# EARM01.net
KiCad netlist of a schematic drawn in EAGLE
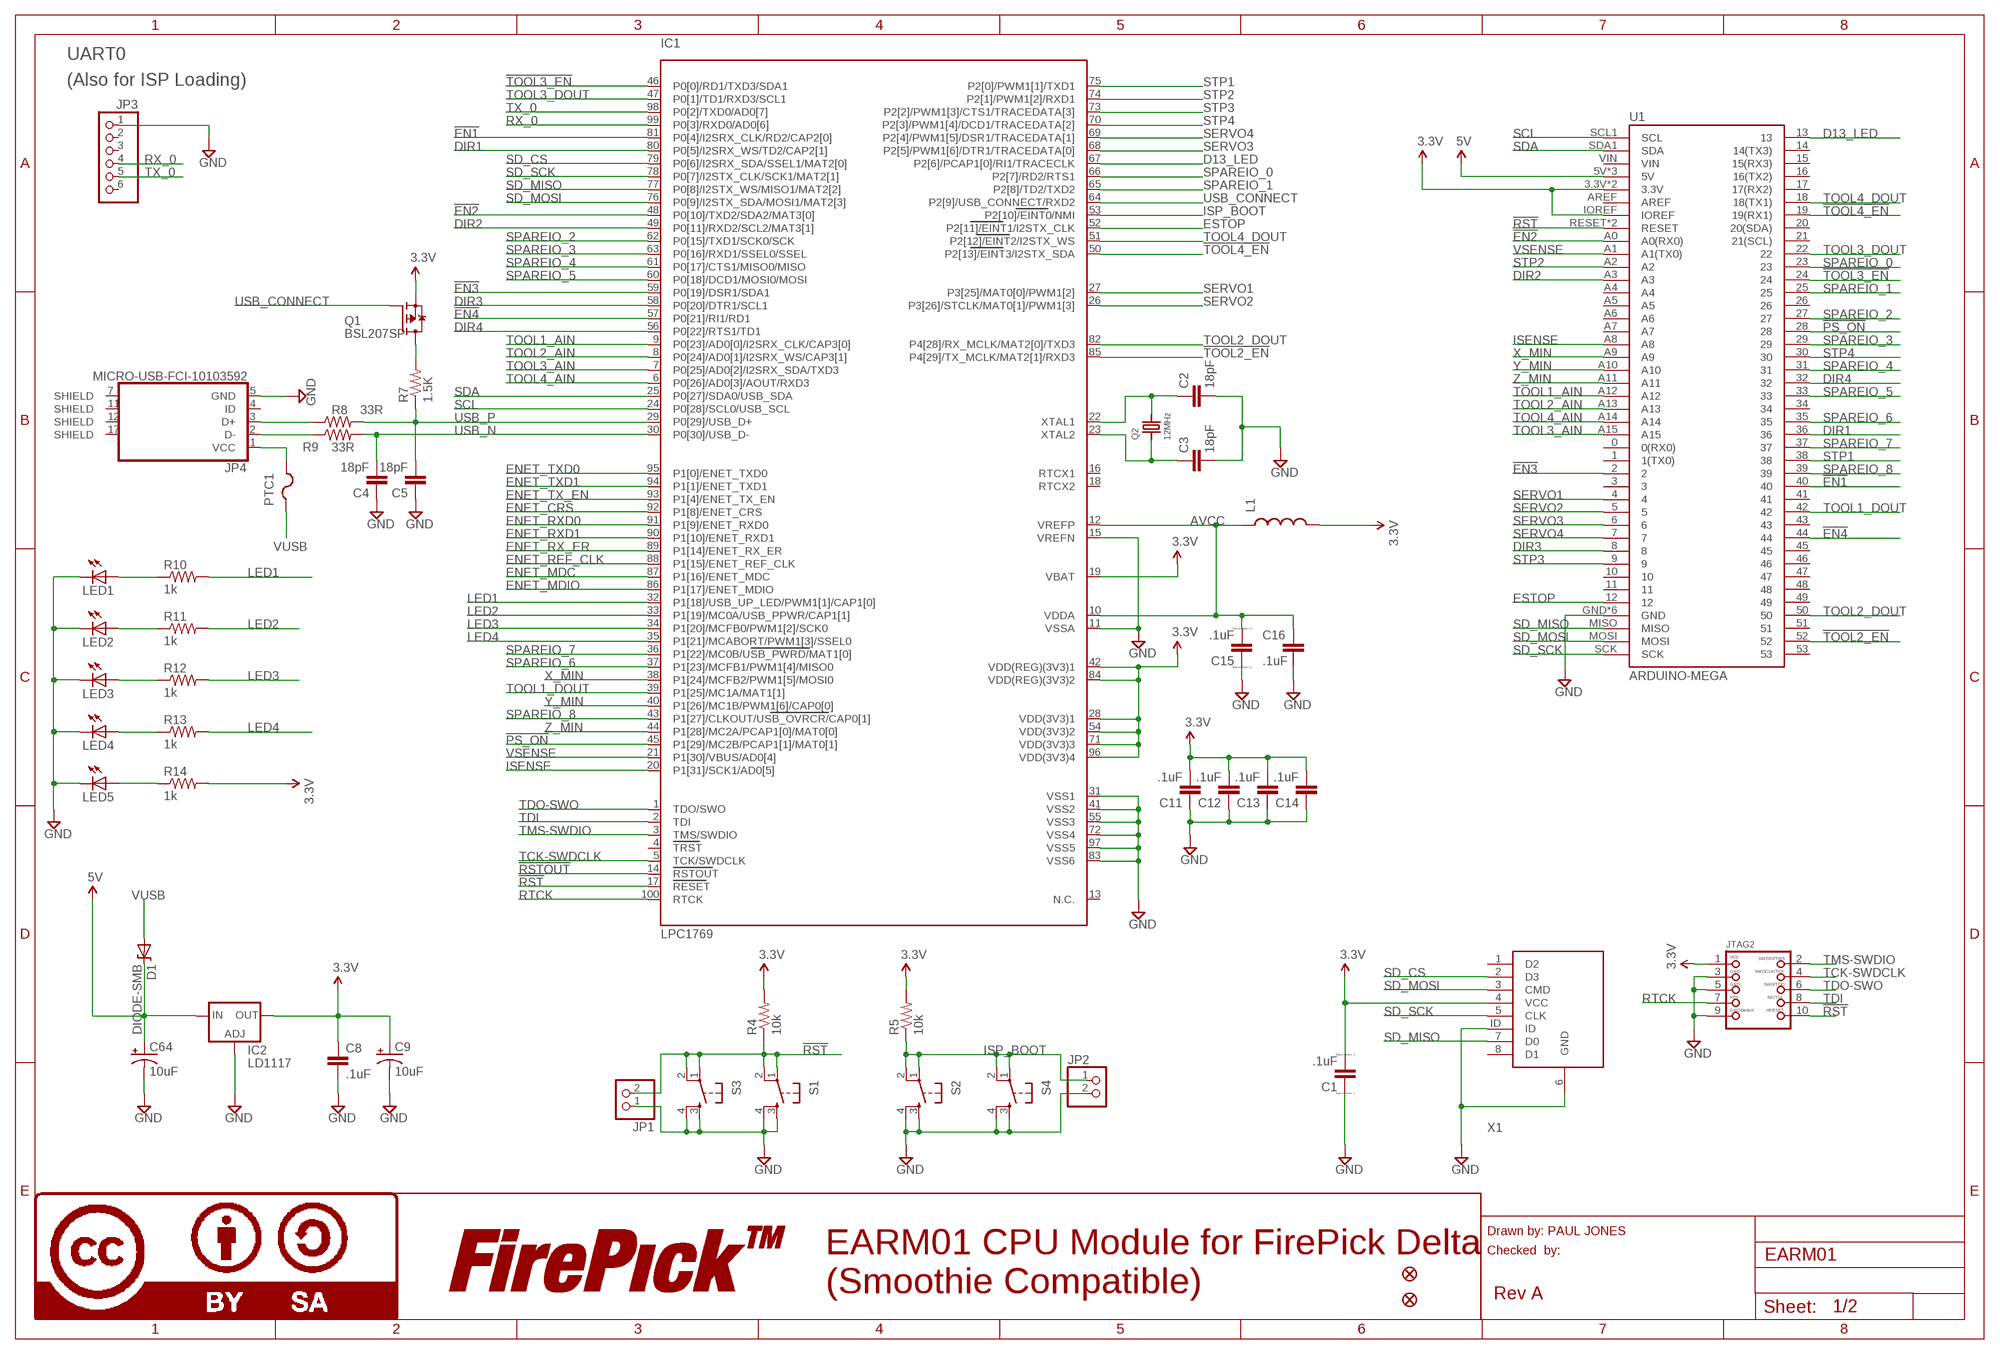
[diagram p0: schematic, sheet 1]
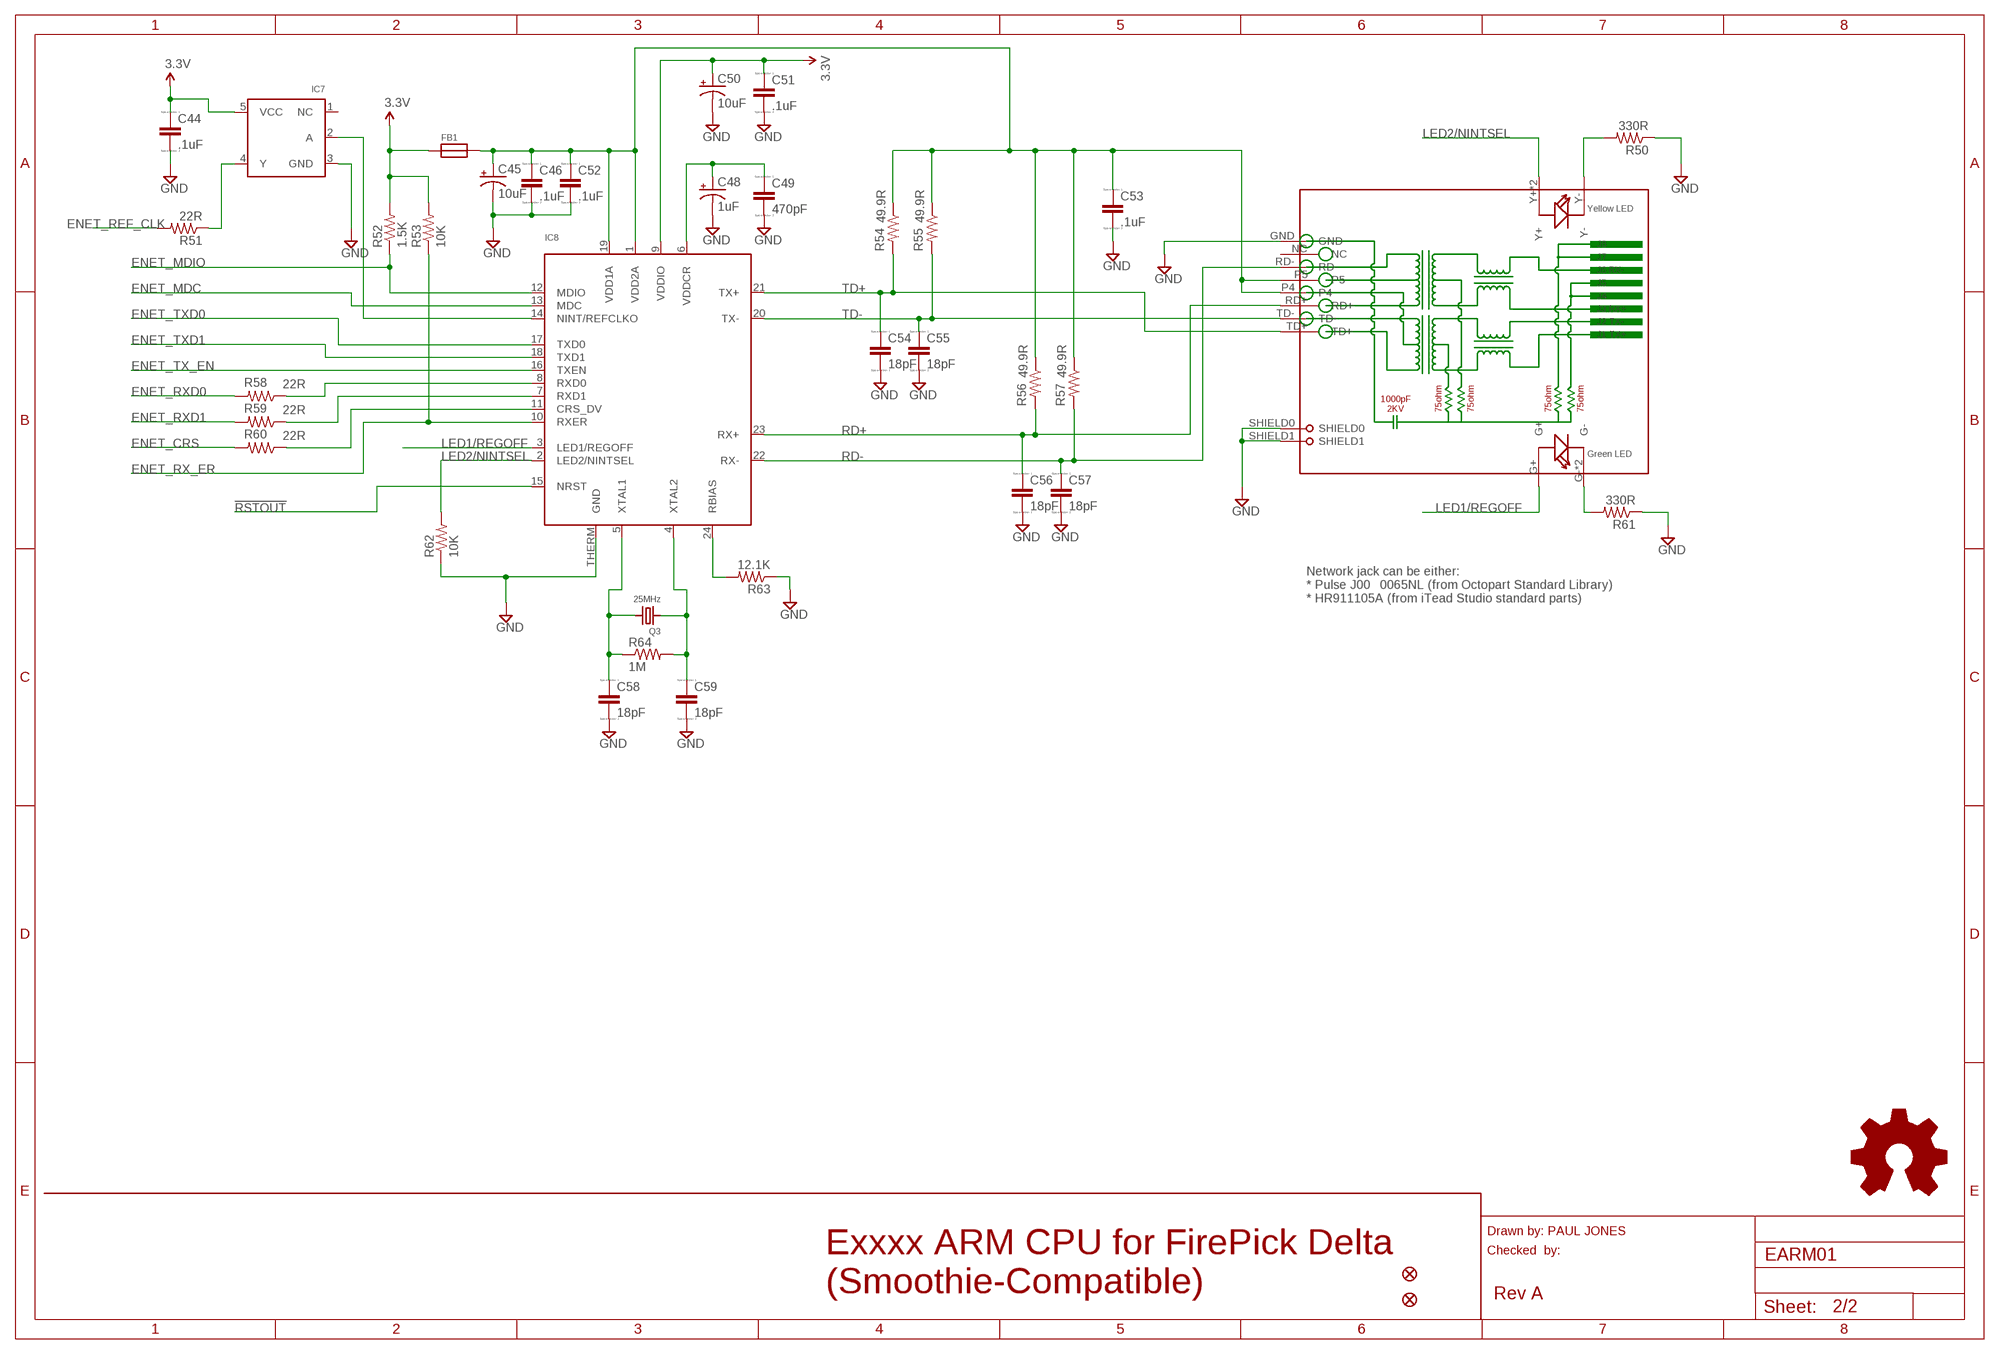
[diagram p1: schematic, sheet 2]

(export (version "E")
  (design (tool "Eeschema 10.0.6"))
  (components
    (comp (ref "C44")
      (value ".1uF")
      (footprint "eagle-import:C0603")
      (libsource (lib "eagle-import") (part "resistor_C-EUC0603"))
    )
    (comp (ref "C45")
      (value "10uF")
      (footprint "eagle-import:EIA3216")
      (libsource (lib "eagle-import") (part "CAP_POL1206"))
    )
    (comp (ref "C46")
      (value ".1uF")
      (footprint "eagle-import:C0603")
      (libsource (lib "eagle-import") (part "resistor_C-EUC0603"))
    )
    (comp (ref "C48")
      (value "1uF")
      (footprint "eagle-import:EIA3216")
      (libsource (lib "eagle-import") (part "CAP_POL1206"))
    )
    (comp (ref "C49")
      (value "470pF")
      (footprint "eagle-import:C0603K")
      (libsource (lib "eagle-import") (part "resistor_C-EUC0603K"))
    )
    (comp (ref "C50")
      (value "10uF")
      (footprint "eagle-import:EIA3216")
      (libsource (lib "eagle-import") (part "CAP_POL1206"))
    )
    (comp (ref "C51")
      (value ".1uF")
      (footprint "eagle-import:C0603")
      (libsource (lib "eagle-import") (part "resistor_C-EUC0603"))
    )
    (comp (ref "C52")
      (value ".1uF")
      (footprint "eagle-import:C0603")
      (libsource (lib "eagle-import") (part "resistor_C-EUC0603"))
    )
    (comp (ref "C53")
      (value ".1uF")
      (footprint "eagle-import:C0603")
      (libsource (lib "eagle-import") (part "resistor_C-EUC0603"))
    )
    (comp (ref "C54")
      (value "18pF")
      (footprint "eagle-import:C0603")
      (libsource (lib "eagle-import") (part "resistor_C-EUC0603"))
    )
    (comp (ref "C55")
      (value "18pF")
      (footprint "eagle-import:C0603")
      (libsource (lib "eagle-import") (part "resistor_C-EUC0603"))
    )
    (comp (ref "C56")
      (value "18pF")
      (footprint "eagle-import:C0603")
      (libsource (lib "eagle-import") (part "resistor_C-EUC0603"))
    )
    (comp (ref "C57")
      (value "18pF")
      (footprint "eagle-import:C0603")
      (libsource (lib "eagle-import") (part "resistor_C-EUC0603"))
    )
    (comp (ref "C58")
      (value "18pF")
      (footprint "eagle-import:C0603")
      (libsource (lib "eagle-import") (part "resistor_C-EUC0603"))
    )
    (comp (ref "C59")
      (value "18pF")
      (footprint "eagle-import:C0603")
      (libsource (lib "eagle-import") (part "resistor_C-EUC0603"))
    )
    (comp (ref "FB1")
      (value "FERRITE")
      (footprint "eagle-import:0603")
      (libsource (lib "eagle-import") (part "FERRITE"))
    )
    (comp (ref "FID17")
      (value "FIDUCIAL1X2")
      (footprint "eagle-import:FIDUCIAL-1X2")
      (libsource (lib "eagle-import") (part "FIDUCIAL1X2"))
    )
    (comp (ref "FID18")
      (value "FIDUCIAL1X2")
      (footprint "eagle-import:FIDUCIAL-1X2")
      (libsource (lib "eagle-import") (part "FIDUCIAL1X2"))
    )
    (comp (ref "IC7")
      (value "74LVC1G04")
      (footprint "eagle-import:SOT23-5")
      (libsource (lib "eagle-import") (part "74LVC1G04"))
    )
    (comp (ref "IC8")
      (value "LAN8720")
      (footprint "eagle-import:QFN24_4MM")
      (libsource (lib "eagle-import") (part "LAN8720"))
    )
    (comp (ref "LOGO10")
      (value "LOGO-OSHWSMALL")
      (footprint "eagle-import:LOGO-OSHW-SMALL")
      (libsource (lib "eagle-import") (part "LOGO-OSHWSMALL"))
    )
    (comp (ref "Q3")
      (value "25MHz")
      (footprint "eagle-import:CRYSTAL_3.2X2.5")
      (libsource (lib "eagle-import") (part "CRYSTALTHIN"))
    )
    (comp (ref "R50")
      (value "330R")
      (footprint "eagle-import:R0603")
      (libsource (lib "eagle-import") (part "R-US_R0603"))
    )
    (comp (ref "R51")
      (value "22R")
      (footprint "eagle-import:R0603")
      (libsource (lib "eagle-import") (part "R-US_R0603"))
    )
    (comp (ref "R52")
      (value "1.5K")
      (footprint "eagle-import:R0603")
      (libsource (lib "eagle-import") (part "R-US_R0603"))
    )
    (comp (ref "R53")
      (value "10K")
      (footprint "eagle-import:R0603")
      (libsource (lib "eagle-import") (part "R-US_R0603"))
    )
    (comp (ref "R54")
      (value "49.9R")
      (footprint "eagle-import:R0603")
      (libsource (lib "eagle-import") (part "R-US_R0603"))
    )
    (comp (ref "R55")
      (value "49.9R")
      (footprint "eagle-import:R0603")
      (libsource (lib "eagle-import") (part "R-US_R0603"))
    )
    (comp (ref "R56")
      (value "49.9R")
      (footprint "eagle-import:R0603")
      (libsource (lib "eagle-import") (part "R-US_R0603"))
    )
    (comp (ref "R57")
      (value "49.9R")
      (footprint "eagle-import:R0603")
      (libsource (lib "eagle-import") (part "R-US_R0603"))
    )
    (comp (ref "R58")
      (value "22R")
      (footprint "eagle-import:R0603")
      (libsource (lib "eagle-import") (part "R-US_R0603"))
    )
    (comp (ref "R59")
      (value "22R")
      (footprint "eagle-import:R0603")
      (libsource (lib "eagle-import") (part "R-US_R0603"))
    )
    (comp (ref "R60")
      (value "22R")
      (footprint "eagle-import:R0603")
      (libsource (lib "eagle-import") (part "R-US_R0603"))
    )
    (comp (ref "R61")
      (value "330R")
      (footprint "eagle-import:R0603")
      (libsource (lib "eagle-import") (part "R-US_R0603"))
    )
    (comp (ref "R62")
      (value "10K")
      (footprint "eagle-import:R0603")
      (libsource (lib "eagle-import") (part "R-US_R0603"))
    )
    (comp (ref "R63")
      (value "12.1K")
      (footprint "eagle-import:R0603")
      (libsource (lib "eagle-import") (part "R-US_R0603"))
    )
    (comp (ref "R64")
      (value "1M")
      (footprint "eagle-import:R0603")
      (libsource (lib "eagle-import") (part "R-US_R0603"))
    )
    (comp (ref "RJ1")
      (value "HR911105A")
      (footprint "eagle-import:HR911105A")
      (libsource (lib "eagle-import") (part "HR911105A"))
    )
    (comp (ref "C1")
      (value ".1uF")
      (footprint "eagle-import:C0603")
      (libsource (lib "eagle-import") (part "resistor_C-EUC0603"))
    )
    (comp (ref "C2")
      (value "18pF")
      (footprint "eagle-import:C0603")
      (libsource (lib "eagle-import") (part "C-EUC0603"))
    )
    (comp (ref "C3")
      (value "18pF")
      (footprint "eagle-import:C0603")
      (libsource (lib "eagle-import") (part "C-EUC0603"))
    )
    (comp (ref "C4")
      (value "18pF")
      (footprint "eagle-import:C0603")
      (libsource (lib "eagle-import") (part "C-EUC0603"))
    )
    (comp (ref "C5")
      (value "18pF")
      (footprint "eagle-import:C0603")
      (libsource (lib "eagle-import") (part "C-EUC0603"))
    )
    (comp (ref "C8")
      (value ".1uF")
      (footprint "eagle-import:C0603")
      (libsource (lib "eagle-import") (part "C-EUC0603"))
    )
    (comp (ref "C9")
      (value "10uF")
      (footprint "eagle-import:EIA3216")
      (libsource (lib "eagle-import") (part "CAP_POL1206"))
    )
    (comp (ref "C11")
      (value ".1uF")
      (footprint "eagle-import:C0603")
      (libsource (lib "eagle-import") (part "C-EUC0603"))
    )
    (comp (ref "C12")
      (value ".1uF")
      (footprint "eagle-import:C0603")
      (libsource (lib "eagle-import") (part "C-EUC0603"))
    )
    (comp (ref "C13")
      (value ".1uF")
      (footprint "eagle-import:C0603")
      (libsource (lib "eagle-import") (part "C-EUC0603"))
    )
    (comp (ref "C14")
      (value ".1uF")
      (footprint "eagle-import:C0603")
      (libsource (lib "eagle-import") (part "C-EUC0603"))
    )
    (comp (ref "C15")
      (value ".1uF")
      (footprint "eagle-import:C0603")
      (libsource (lib "eagle-import") (part "resistor_C-EUC0603"))
    )
    (comp (ref "C16")
      (value ".1uF")
      (footprint "eagle-import:C0603")
      (libsource (lib "eagle-import") (part "C-EUC0603"))
    )
    (comp (ref "C64")
      (value "10uF")
      (footprint "eagle-import:EIA3216")
      (libsource (lib "eagle-import") (part "CAP_POL1206"))
    )
    (comp (ref "D1")
      (value "DIODE-SMB")
      (footprint "eagle-import:SMB-DIODE")
      (libsource (lib "eagle-import") (part "DIODE-ZENERSMB"))
    )
    (comp (ref "FID5")
      (value "FIDUCIAL1X2")
      (footprint "eagle-import:FIDUCIAL-1X2")
      (libsource (lib "eagle-import") (part "FIDUCIAL1X2"))
    )
    (comp (ref "FID6")
      (value "FIDUCIAL1X2")
      (footprint "eagle-import:FIDUCIAL-1X2")
      (libsource (lib "eagle-import") (part "FIDUCIAL1X2"))
    )
    (comp (ref "IC1")
      (value "LPC1769")
      (footprint "eagle-import:LQFP100")
      (libsource (lib "eagle-import") (part "LPC1768"))
    )
    (comp (ref "IC2")
      (value "LD1117")
      (footprint "eagle-import:SOT223")
      (libsource (lib "eagle-import") (part "LD117A?S12TR"))
    )
    (comp (ref "JP1")
      (value "PINHD-1X2")
      (footprint "eagle-import:1X02")
      (libsource (lib "eagle-import") (part "PINHD-1X2"))
    )
    (comp (ref "JP2")
      (value "PINHD-1X2")
      (footprint "eagle-import:1X02")
      (libsource (lib "eagle-import") (part "PINHD-1X2"))
    )
    (comp (ref "JP3")
      (value "PINHD-1X6")
      (footprint "eagle-import:1X06")
      (libsource (lib "eagle-import") (part "PINHD-1X6"))
    )
    (comp (ref "JP4")
      (value "MICRO-USB-FCI-10103592")
      (footprint "eagle-import:MICRO-USB-FCI-10103592")
      (libsource (lib "eagle-import") (part "MICRO-USB-FCI-10103592"))
    )
    (comp (ref "JTAG2")
      (value "JTAG-CORTEXM3")
      (footprint "eagle-import:2X05_1.27MM_SMT")
      (libsource (lib "eagle-import") (part "JTAG-CORTEXM3"))
    )
    (comp (ref "L1")
      (value "INDUCTOR0603")
      (footprint "eagle-import:0603")
      (libsource (lib "eagle-import") (part "INDUCTOR0603"))
    )
    (comp (ref "LED1")
      (value "LED")
      (footprint "eagle-import:LED-1206-BOTTOM")
      (libsource (lib "eagle-import") (part "LED"))
    )
    (comp (ref "LED2")
      (value "LED")
      (footprint "eagle-import:LED-1206-BOTTOM")
      (libsource (lib "eagle-import") (part "LED"))
    )
    (comp (ref "LED3")
      (value "LED")
      (footprint "eagle-import:LED-1206-BOTTOM")
      (libsource (lib "eagle-import") (part "LED"))
    )
    (comp (ref "LED4")
      (value "LED")
      (footprint "eagle-import:LED-1206-BOTTOM")
      (libsource (lib "eagle-import") (part "LED"))
    )
    (comp (ref "LED5")
      (value "LED")
      (footprint "eagle-import:LED-1206-BOTTOM")
      (libsource (lib "eagle-import") (part "LED"))
    )
    (comp (ref "LOGO4")
      (value "LOGO-FIREPICKMEDIUM")
      (footprint "eagle-import:LOGO-FIREPICK-MEDIUM")
      (libsource (lib "eagle-import") (part "LOGO-FIREPICKMEDIUM"))
    )
    (comp (ref "LOGO6")
      (value "LOGO-CC-BY-SAMEDIUM")
      (footprint "eagle-import:LOGO-CC-BY-SA-MEDIUM")
      (libsource (lib "eagle-import") (part "LOGO-CC-BY-SAMEDIUM"))
    )
    (comp (ref "PTC1")
      (value "PTCFUSE-1812")
      (footprint "eagle-import:1812")
      (libsource (lib "eagle-import") (part "PTCFUSE-1812"))
    )
    (comp (ref "Q1")
      (value "BSL207SP")
      (footprint "eagle-import:SC74_INFINEON")
      (libsource (lib "eagle-import") (part "BSL207SP"))
    )
    (comp (ref "Q2")
      (value "12MHz")
      (footprint "eagle-import:CRYSTAL_3.2X2.5")
      (libsource (lib "eagle-import") (part "CRYSTALTHIN"))
    )
    (comp (ref "R4")
      (value "10k")
      (footprint "eagle-import:R0603")
      (libsource (lib "eagle-import") (part "R-US_R0603"))
    )
    (comp (ref "R5")
      (value "10k")
      (footprint "eagle-import:R0603")
      (libsource (lib "eagle-import") (part "R-US_R0603"))
    )
    (comp (ref "R7")
      (value "1.5K")
      (footprint "eagle-import:R0603")
      (libsource (lib "eagle-import") (part "R-US_R0603"))
    )
    (comp (ref "R8")
      (value "33R")
      (footprint "eagle-import:R0603")
      (libsource (lib "eagle-import") (part "R-US_R0603"))
    )
    (comp (ref "R9")
      (value "33R")
      (footprint "eagle-import:R0603")
      (libsource (lib "eagle-import") (part "R-US_R0603"))
    )
    (comp (ref "R10")
      (value "1k")
      (footprint "eagle-import:R0603")
      (libsource (lib "eagle-import") (part "R-US_R0603"))
    )
    (comp (ref "R11")
      (value "1k")
      (footprint "eagle-import:R0603")
      (libsource (lib "eagle-import") (part "R-US_R0603"))
    )
    (comp (ref "R12")
      (value "1k")
      (footprint "eagle-import:R0603")
      (libsource (lib "eagle-import") (part "R-US_R0603"))
    )
    (comp (ref "R13")
      (value "1k")
      (footprint "eagle-import:R0603")
      (libsource (lib "eagle-import") (part "R-US_R0603"))
    )
    (comp (ref "R14")
      (value "1k")
      (footprint "eagle-import:R0603")
      (libsource (lib "eagle-import") (part "R-US_R0603"))
    )
    (comp (ref "S1")
      (value "TAC_SWITCHSMD")
      (footprint "eagle-import:TACTILE_SWITCH_SMD")
      (libsource (lib "eagle-import") (part "TAC_SWITCHSMD"))
    )
    (comp (ref "S2")
      (value "TAC_SWITCHSMD")
      (footprint "eagle-import:TACTILE_SWITCH_SMD")
      (libsource (lib "eagle-import") (part "TAC_SWITCHSMD"))
    )
    (comp (ref "S3")
      (value "TAC_SWITCHSMD")
      (footprint "eagle-import:TACTILE_SWITCH_SMD")
      (libsource (lib "eagle-import") (part "TAC_SWITCHSMD"))
    )
    (comp (ref "S4")
      (value "TAC_SWITCHSMD")
      (footprint "eagle-import:TACTILE_SWITCH_SMD")
      (libsource (lib "eagle-import") (part "TAC_SWITCHSMD"))
    )
    (comp (ref "U1")
      (value "ARDUINO-MEGA")
      (footprint "eagle-import:ARDUINO_MEGA_NEW")
      (libsource (lib "eagle-import") (part "ARDUINO-MEGA"))
    )
    (comp (ref "X1")
      (value "ST9S008V4AR1500")
      (footprint "eagle-import:ST9S008V4AR1500")
      (libsource (lib "eagle-import") (part "ST9S008V4AR1500"))
    )
  )
  (nets
    (net (code "1") (name "3.3V") (class "Default")
      (node (ref "C1") (pin "2") (pinfunction "2_2") (pintype "passive"))
      (node (ref "C11") (pin "2") (pinfunction "2_2") (pintype "passive"))
      (node (ref "C12") (pin "2") (pinfunction "2_2") (pintype "passive"))
      (node (ref "C13") (pin "2") (pinfunction "2_2") (pintype "passive"))
      (node (ref "C14") (pin "2") (pinfunction "2_2") (pintype "passive"))
      (node (ref "C44") (pin "1") (pinfunction "1_1") (pintype "passive"))
      (node (ref "C50") (pin "A") (pinfunction "+_A") (pintype "passive"))
      (node (ref "C51") (pin "1") (pinfunction "1_1") (pintype "passive"))
      (node (ref "C8") (pin "1") (pinfunction "1_1") (pintype "passive"))
      (node (ref "C9") (pin "A") (pinfunction "+_A") (pintype "passive"))
      (node (ref "FB1") (pin "1") (pinfunction "P$1_1") (pintype "bidirectional"))
      (node (ref "IC1") (pin "19") (pinfunction "VBAT_19") (pintype "bidirectional"))
      (node (ref "IC1") (pin "28") (pinfunction "VDD(3V3)1_28") (pintype "bidirectional"))
      (node (ref "IC1") (pin "42") (pinfunction "VDD(REG)(3V3)1_42") (pintype "bidirectional"))
      (node (ref "IC1") (pin "54") (pinfunction "VDD(3V3)2_54") (pintype "bidirectional"))
      (node (ref "IC1") (pin "71") (pinfunction "VDD(3V3)3_71") (pintype "bidirectional"))
      (node (ref "IC1") (pin "84") (pinfunction "VDD(REG)(3V3)2_84") (pintype "bidirectional"))
      (node (ref "IC1") (pin "96") (pinfunction "VDD(3V3)4_96") (pintype "bidirectional"))
      (node (ref "IC2") (pin "4") (pinfunction "OUT_4") (pintype "passive"))
      (node (ref "IC7") (pin "5") (pinfunction "VCC_5") (pintype "power_in"))
      (node (ref "IC8") (pin "9") (pinfunction "VDDIO_9") (pintype "bidirectional"))
      (node (ref "JTAG2") (pin "1") (pinfunction "1_1") (pintype "passive"))
      (node (ref "L1") (pin "2") (pinfunction "2_2") (pintype "passive"))
      (node (ref "Q1") (pin "4") (pinfunction "S_4") (pintype "passive"))
      (node (ref "R14") (pin "2") (pinfunction "2_2") (pintype "passive"))
      (node (ref "R4") (pin "2") (pinfunction "2_2") (pintype "passive"))
      (node (ref "R5") (pin "2") (pinfunction "2_2") (pintype "passive"))
      (node (ref "R52") (pin "2") (pinfunction "2_2") (pintype "passive"))
      (node (ref "R53") (pin "2") (pinfunction "2_2") (pintype "passive"))
      (node (ref "U1") (pin "3.3V") (pinfunction "3.3V_3.3V") (pintype "bidirectional"))
      (node (ref "U1") (pin "IOREF") (pinfunction "IOREF_IOREF") (pintype "bidirectional"))
      (node (ref "U1") (pin "VCC") (pinfunction "3.3V_VCC") (pintype "bidirectional"))
      (node (ref "X1") (pin "4") (pinfunction "VCC_4") (pintype "input"))
    )
    (net (code "2") (name "5V") (class "Default")
      (node (ref "C64") (pin "A") (pinfunction "+_A") (pintype "passive"))
      (node (ref "D1") (pin "C") (pinfunction "C_C") (pintype "passive"))
      (node (ref "IC2") (pin "3") (pinfunction "IN_3") (pintype "input"))
      (node (ref "U1") (pin "5V") (pinfunction "5V_5V") (pintype "bidirectional"))
      (node (ref "U1") (pin "5V@1") (pinfunction "5V_5V@1") (pintype "bidirectional"))
      (node (ref "U1") (pin "5V@2") (pinfunction "5V_5V@2") (pintype "bidirectional"))
    )
    (net (code "3") (name "AVCC") (class "Default")
      (node (ref "C15") (pin "2") (pinfunction "2_2") (pintype "passive"))
      (node (ref "C16") (pin "1") (pinfunction "1_1") (pintype "passive"))
      (node (ref "IC1") (pin "10") (pinfunction "VDDA_10") (pintype "bidirectional"))
      (node (ref "IC1") (pin "12") (pinfunction "VREFP_12") (pintype "bidirectional"))
      (node (ref "L1") (pin "1") (pinfunction "1_1") (pintype "passive"))
    )
    (net (code "4") (name "D13_LED") (class "Default")
      (node (ref "IC1") (pin "67") (pinfunction "P2[6]/PCAP1[0]/RI1/TRACECLK_67") (pintype "bidirectional"))
      (node (ref "U1") (pin "13") (pinfunction "13_13") (pintype "bidirectional"))
    )
    (net (code "5") (name "DIR1") (class "Default")
      (node (ref "IC1") (pin "80") (pinfunction "P0[5]/I2SRX_WS/TD2/CAP2[1]_80") (pintype "bidirectional"))
      (node (ref "U1") (pin "36") (pinfunction "36_36") (pintype "bidirectional"))
    )
    (net (code "6") (name "DIR2") (class "Default")
      (node (ref "IC1") (pin "49") (pinfunction "P0[11]/RXD2/SCL2/MAT3[1]_49") (pintype "bidirectional"))
      (node (ref "U1") (pin "A3") (pinfunction "A3_A3") (pintype "bidirectional"))
    )
    (net (code "7") (name "DIR3") (class "Default")
      (node (ref "IC1") (pin "58") (pinfunction "P0[20]/DTR1/SCL1_58") (pintype "bidirectional"))
      (node (ref "U1") (pin "8") (pinfunction "8_8") (pintype "bidirectional"))
    )
    (net (code "8") (name "DIR4") (class "Default")
      (node (ref "IC1") (pin "56") (pinfunction "P0[22]/RTS1/TD1_56") (pintype "bidirectional"))
      (node (ref "U1") (pin "32") (pinfunction "32_32") (pintype "bidirectional"))
    )
    (net (code "9") (name "ENET_CRS") (class "Default")
      (node (ref "IC1") (pin "92") (pinfunction "P1[8]/ENET_CRS_92") (pintype "bidirectional"))
      (node (ref "R60") (pin "2") (pinfunction "2_2") (pintype "passive"))
    )
    (net (code "10") (name "ENET_MDC") (class "Default")
      (node (ref "IC1") (pin "87") (pinfunction "P1[16]/ENET_MDC_87") (pintype "bidirectional"))
      (node (ref "IC8") (pin "13") (pinfunction "MDC_13") (pintype "bidirectional"))
    )
    (net (code "11") (name "ENET_MDIO") (class "Default")
      (node (ref "IC1") (pin "86") (pinfunction "P1[17]/ENET_MDIO_86") (pintype "bidirectional"))
      (node (ref "IC8") (pin "12") (pinfunction "MDIO_12") (pintype "bidirectional"))
      (node (ref "R52") (pin "1") (pinfunction "1_1") (pintype "passive"))
    )
    (net (code "12") (name "ENET_REF_CLK") (class "Default")
      (node (ref "IC1") (pin "88") (pinfunction "P1[15]/ENET_REF_CLK_88") (pintype "bidirectional"))
      (node (ref "R51") (pin "2") (pinfunction "2_2") (pintype "passive"))
    )
    (net (code "13") (name "ENET_RXD0") (class "Default")
      (node (ref "IC1") (pin "91") (pinfunction "P1[9]/ENET_RXD0_91") (pintype "bidirectional"))
      (node (ref "R58") (pin "2") (pinfunction "2_2") (pintype "passive"))
    )
    (net (code "14") (name "ENET_RXD1") (class "Default")
      (node (ref "IC1") (pin "90") (pinfunction "P1[10]/ENET_RXD1_90") (pintype "bidirectional"))
      (node (ref "R59") (pin "2") (pinfunction "2_2") (pintype "passive"))
    )
    (net (code "15") (name "ENET_RX_ER") (class "Default")
      (node (ref "IC1") (pin "89") (pinfunction "P1[14]/ENET_RX_ER_89") (pintype "bidirectional"))
      (node (ref "IC8") (pin "10") (pinfunction "RXER_10") (pintype "bidirectional"))
      (node (ref "R53") (pin "1") (pinfunction "1_1") (pintype "passive"))
    )
    (net (code "16") (name "ENET_TXD0") (class "Default")
      (node (ref "IC1") (pin "95") (pinfunction "P1[0]/ENET_TXD0_95") (pintype "bidirectional"))
      (node (ref "IC8") (pin "17") (pinfunction "TXD0_17") (pintype "bidirectional"))
    )
    (net (code "17") (name "ENET_TXD1") (class "Default")
      (node (ref "IC1") (pin "94") (pinfunction "P1[1]/ENET_TXD1_94") (pintype "bidirectional"))
      (node (ref "IC8") (pin "18") (pinfunction "TXD1_18") (pintype "bidirectional"))
    )
    (net (code "18") (name "ENET_TX_EN") (class "Default")
      (node (ref "IC1") (pin "93") (pinfunction "P1[4]/ENET_TX_EN_93") (pintype "bidirectional"))
      (node (ref "IC8") (pin "16") (pinfunction "TXEN_16") (pintype "bidirectional"))
    )
    (net (code "19") (name "ESTOP") (class "Default")
      (node (ref "IC1") (pin "52") (pinfunction "P2[11]/EINT1/I2STX_CLK_52") (pintype "bidirectional"))
      (node (ref "U1") (pin "12") (pinfunction "12_12") (pintype "bidirectional"))
    )
    (net (code "20") (name "GND") (class "Default")
      (node (ref "C1") (pin "1") (pinfunction "1_1") (pintype "passive"))
      (node (ref "C11") (pin "1") (pinfunction "1_1") (pintype "passive"))
      (node (ref "C12") (pin "1") (pinfunction "1_1") (pintype "passive"))
      (node (ref "C13") (pin "1") (pinfunction "1_1") (pintype "passive"))
      (node (ref "C14") (pin "1") (pinfunction "1_1") (pintype "passive"))
      (node (ref "C15") (pin "1") (pinfunction "1_1") (pintype "passive"))
      (node (ref "C16") (pin "2") (pinfunction "2_2") (pintype "passive"))
      (node (ref "C2") (pin "2") (pinfunction "2_2") (pintype "passive"))
      (node (ref "C3") (pin "2") (pinfunction "2_2") (pintype "passive"))
      (node (ref "C4") (pin "1") (pinfunction "1_1") (pintype "passive"))
      (node (ref "C44") (pin "2") (pinfunction "2_2") (pintype "passive"))
      (node (ref "C45") (pin "C") (pinfunction "-_C") (pintype "passive"))
      (node (ref "C46") (pin "2") (pinfunction "2_2") (pintype "passive"))
      (node (ref "C48") (pin "C") (pinfunction "-_C") (pintype "passive"))
      (node (ref "C49") (pin "2") (pinfunction "2_2") (pintype "passive"))
      (node (ref "C5") (pin "1") (pinfunction "1_1") (pintype "passive"))
      (node (ref "C50") (pin "C") (pinfunction "-_C") (pintype "passive"))
      (node (ref "C51") (pin "2") (pinfunction "2_2") (pintype "passive"))
      (node (ref "C52") (pin "2") (pinfunction "2_2") (pintype "passive"))
      (node (ref "C53") (pin "2") (pinfunction "2_2") (pintype "passive"))
      (node (ref "C54") (pin "2") (pinfunction "2_2") (pintype "passive"))
      (node (ref "C55") (pin "2") (pinfunction "2_2") (pintype "passive"))
      (node (ref "C56") (pin "2") (pinfunction "2_2") (pintype "passive"))
      (node (ref "C57") (pin "2") (pinfunction "2_2") (pintype "passive"))
      (node (ref "C58") (pin "2") (pinfunction "2_2") (pintype "passive"))
      (node (ref "C59") (pin "2") (pinfunction "2_2") (pintype "passive"))
      (node (ref "C64") (pin "C") (pinfunction "-_C") (pintype "passive"))
      (node (ref "C8") (pin "2") (pinfunction "2_2") (pintype "passive"))
      (node (ref "C9") (pin "C") (pinfunction "-_C") (pintype "passive"))
      (node (ref "IC1") (pin "11") (pinfunction "VSSA_11") (pintype "bidirectional"))
      (node (ref "IC1") (pin "15") (pinfunction "VREFN_15") (pintype "bidirectional"))
      (node (ref "IC1") (pin "31") (pinfunction "VSS1_31") (pintype "bidirectional"))
      (node (ref "IC1") (pin "41") (pinfunction "VSS2_41") (pintype "bidirectional"))
      (node (ref "IC1") (pin "55") (pinfunction "VSS3_55") (pintype "bidirectional"))
      (node (ref "IC1") (pin "72") (pinfunction "VSS4_72") (pintype "bidirectional"))
      (node (ref "IC1") (pin "83") (pinfunction "VSS6_83") (pintype "bidirectional"))
      (node (ref "IC1") (pin "97") (pinfunction "VSS5_97") (pintype "bidirectional"))
      (node (ref "IC2") (pin "1") (pinfunction "ADJ_1") (pintype "input"))
      (node (ref "IC7") (pin "3") (pinfunction "GND_3") (pintype "power_in"))
      (node (ref "IC8") (pin "THERM") (pinfunction "GND_THERM") (pintype "bidirectional"))
      (node (ref "JP1") (pin "1") (pinfunction "1_1") (pintype "passive"))
      (node (ref "JP2") (pin "2") (pinfunction "2_2") (pintype "passive"))
      (node (ref "JP3") (pin "1") (pinfunction "1_1") (pintype "passive"))
      (node (ref "JP4") (pin "5") (pinfunction "GND_5") (pintype "bidirectional"))
      (node (ref "JTAG2") (pin "3") (pinfunction "3_3") (pintype "passive"))
      (node (ref "JTAG2") (pin "5") (pinfunction "5_5") (pintype "passive"))
      (node (ref "JTAG2") (pin "9") (pinfunction "9_9") (pintype "passive"))
      (node (ref "LED1") (pin "C") (pinfunction "C_C") (pintype "passive"))
      (node (ref "LED2") (pin "C") (pinfunction "C_C") (pintype "passive"))
      (node (ref "LED3") (pin "C") (pinfunction "C_C") (pintype "passive"))
      (node (ref "LED4") (pin "C") (pinfunction "C_C") (pintype "passive"))
      (node (ref "LED5") (pin "C") (pinfunction "C_C") (pintype "passive"))
      (node (ref "R50") (pin "1") (pinfunction "1_1") (pintype "passive"))
      (node (ref "R61") (pin "1") (pinfunction "1_1") (pintype "passive"))
      (node (ref "R62") (pin "1") (pinfunction "1_1") (pintype "passive"))
      (node (ref "R63") (pin "1") (pinfunction "1_1") (pintype "passive"))
      (node (ref "RJ1") (pin "GND") (pinfunction "GND_GND") (pintype "bidirectional"))
      (node (ref "RJ1") (pin "SHIELD0") (pinfunction "SHIELD0_SHIELD0") (pintype "bidirectional"))
      (node (ref "RJ1") (pin "SHIELD1") (pinfunction "SHIELD1_SHIELD1") (pintype "bidirectional"))
      (node (ref "S1") (pin "3") (pinfunction "3_3") (pintype "passive"))
      (node (ref "S1") (pin "4") (pinfunction "4_4") (pintype "passive"))
      (node (ref "S2") (pin "3") (pinfunction "3_3") (pintype "passive"))
      (node (ref "S2") (pin "4") (pinfunction "4_4") (pintype "passive"))
      (node (ref "S3") (pin "3") (pinfunction "3_3") (pintype "passive"))
      (node (ref "S3") (pin "4") (pinfunction "4_4") (pintype "passive"))
      (node (ref "S4") (pin "3") (pinfunction "3_3") (pintype "passive"))
      (node (ref "S4") (pin "4") (pinfunction "4_4") (pintype "passive"))
      (node (ref "U1") (pin "GND") (pinfunction "GND_GND") (pintype "bidirectional"))
      (node (ref "U1") (pin "GND@0") (pinfunction "GND_GND@0") (pintype "bidirectional"))
      (node (ref "U1") (pin "GND@1") (pinfunction "GND_GND@1") (pintype "bidirectional"))
      (node (ref "U1") (pin "GND@2") (pinfunction "GND_GND@2") (pintype "bidirectional"))
      (node (ref "U1") (pin "GND@3") (pinfunction "GND_GND@3") (pintype "bidirectional"))
      (node (ref "U1") (pin "GNDI") (pinfunction "GND_GNDI") (pintype "bidirectional"))
      (node (ref "X1") (pin "6") (pinfunction "GND_6") (pintype "passive"))
      (node (ref "X1") (pin "ID") (pinfunction "ID_ID") (pintype "passive"))
    )
    (net (code "21") (name "ISENSE") (class "Default")
      (node (ref "IC1") (pin "20") (pinfunction "P1[31]/SCK1/AD0[5]_20") (pintype "bidirectional"))
      (node (ref "U1") (pin "A8") (pinfunction "A8_A8") (pintype "bidirectional"))
    )
    (net (code "22") (name "ISP_BOOT") (class "Default")
      (node (ref "IC1") (pin "53") (pinfunction "P2[10]/EINT0/NMI_53") (pintype "bidirectional"))
      (node (ref "JP2") (pin "1") (pinfunction "1_1") (pintype "passive"))
      (node (ref "R5") (pin "1") (pinfunction "1_1") (pintype "passive"))
      (node (ref "S2") (pin "1") (pinfunction "1_1") (pintype "passive"))
      (node (ref "S2") (pin "2") (pinfunction "2_2") (pintype "passive"))
      (node (ref "S4") (pin "1") (pinfunction "1_1") (pintype "passive"))
      (node (ref "S4") (pin "2") (pinfunction "2_2") (pintype "passive"))
    )
    (net (code "23") (name "LED1") (class "Default")
      (node (ref "IC1") (pin "32") (pinfunction "P1[18]/USB_UP_LED/PWM1[1]/CAP1[0]_32") (pintype "bidirectional"))
      (node (ref "R10") (pin "2") (pinfunction "2_2") (pintype "passive"))
    )
    (net (code "24") (name "LED1{slash}REGOFF") (class "Default")
      (node (ref "IC8") (pin "3") (pinfunction "LED1/REGOFF_3") (pintype "bidirectional"))
      (node (ref "RJ1") (pin "G+") (pinfunction "G+_G+") (pintype "bidirectional"))
    )
    (net (code "25") (name "LED2") (class "Default")
      (node (ref "IC1") (pin "33") (pinfunction "P1[19]/MC0A/USB_PPWR/CAP1[1]_33") (pintype "bidirectional"))
      (node (ref "R11") (pin "2") (pinfunction "2_2") (pintype "passive"))
    )
    (net (code "26") (name "LED2{slash}NINTSEL") (class "Default")
      (node (ref "IC8") (pin "2") (pinfunction "LED2/NINTSEL_2") (pintype "bidirectional"))
      (node (ref "R62") (pin "2") (pinfunction "2_2") (pintype "passive"))
      (node (ref "RJ1") (pin "Y+") (pinfunction "Y+_Y+") (pintype "bidirectional"))
      (node (ref "RJ1") (pin "Y++") (pinfunction "Y+_Y++") (pintype "bidirectional"))
    )
    (net (code "27") (name "LED3") (class "Default")
      (node (ref "IC1") (pin "34") (pinfunction "P1[20]/MCFB0/PWM1[2]/SCK0_34") (pintype "bidirectional"))
      (node (ref "R12") (pin "2") (pinfunction "2_2") (pintype "passive"))
    )
    (net (code "28") (name "LED4") (class "Default")
      (node (ref "IC1") (pin "35") (pinfunction "P1[21]/MCABORT/PWM1[3]/SSEL0_35") (pintype "bidirectional"))
      (node (ref "R13") (pin "2") (pinfunction "2_2") (pintype "passive"))
    )
    (net (code "29") (name "Net-(C45-+)") (class "Default")
      (node (ref "C45") (pin "A") (pinfunction "+_A") (pintype "passive"))
      (node (ref "C46") (pin "1") (pinfunction "1_1") (pintype "passive"))
      (node (ref "C52") (pin "1") (pinfunction "1_1") (pintype "passive"))
      (node (ref "C53") (pin "1") (pinfunction "1_1") (pintype "passive"))
      (node (ref "FB1") (pin "2") (pinfunction "P$2_2") (pintype "bidirectional"))
      (node (ref "IC8") (pin "1") (pinfunction "VDD2A_1") (pintype "bidirectional"))
      (node (ref "IC8") (pin "19") (pinfunction "VDD1A_19") (pintype "bidirectional"))
      (node (ref "R54") (pin "1") (pinfunction "1_1") (pintype "passive"))
      (node (ref "R55") (pin "1") (pinfunction "1_1") (pintype "passive"))
      (node (ref "R56") (pin "1") (pinfunction "1_1") (pintype "passive"))
      (node (ref "R57") (pin "1") (pinfunction "1_1") (pintype "passive"))
      (node (ref "RJ1") (pin "P4") (pinfunction "P4_P4") (pintype "bidirectional"))
      (node (ref "RJ1") (pin "P5") (pinfunction "P5_P5") (pintype "bidirectional"))
    )
    (net (code "30") (name "Net-(C48-+)") (class "Default")
      (node (ref "C48") (pin "A") (pinfunction "+_A") (pintype "passive"))
      (node (ref "C49") (pin "1") (pinfunction "1_1") (pintype "passive"))
      (node (ref "IC8") (pin "6") (pinfunction "VDDCR_6") (pintype "bidirectional"))
    )
    (net (code "31") (name "Net-(IC1-XTAL1)") (class "Default")
      (node (ref "C2") (pin "1") (pinfunction "1_1") (pintype "passive"))
      (node (ref "IC1") (pin "22") (pinfunction "XTAL1_22") (pintype "bidirectional"))
      (node (ref "Q2") (pin "2") (pinfunction "2_2") (pintype "passive"))
    )
    (net (code "32") (name "Net-(IC1-XTAL2)") (class "Default")
      (node (ref "C3") (pin "1") (pinfunction "1_1") (pintype "passive"))
      (node (ref "IC1") (pin "23") (pinfunction "XTAL2_23") (pintype "bidirectional"))
      (node (ref "Q2") (pin "1") (pinfunction "1_1") (pintype "passive"))
    )
    (net (code "33") (name "Net-(IC7-A)") (class "Default")
      (node (ref "IC7") (pin "2") (pinfunction "A_2") (pintype "bidirectional"))
      (node (ref "IC8") (pin "14") (pinfunction "NINT/REFCLKO_14") (pintype "bidirectional"))
    )
    (net (code "34") (name "Net-(IC7-Y)") (class "Default")
      (node (ref "IC7") (pin "4") (pinfunction "Y_4") (pintype "bidirectional"))
      (node (ref "R51") (pin "1") (pinfunction "1_1") (pintype "passive"))
    )
    (net (code "35") (name "Net-(IC8-CRS_DV)") (class "Default")
      (node (ref "IC8") (pin "11") (pinfunction "CRS_DV_11") (pintype "bidirectional"))
      (node (ref "R60") (pin "1") (pinfunction "1_1") (pintype "passive"))
    )
    (net (code "36") (name "Net-(IC8-RBIAS)") (class "Default")
      (node (ref "IC8") (pin "24") (pinfunction "RBIAS_24") (pintype "bidirectional"))
      (node (ref "R63") (pin "2") (pinfunction "2_2") (pintype "passive"))
    )
    (net (code "37") (name "Net-(IC8-RXD0)") (class "Default")
      (node (ref "IC8") (pin "8") (pinfunction "RXD0_8") (pintype "bidirectional"))
      (node (ref "R58") (pin "1") (pinfunction "1_1") (pintype "passive"))
    )
    (net (code "38") (name "Net-(IC8-RXD1)") (class "Default")
      (node (ref "IC8") (pin "7") (pinfunction "RXD1_7") (pintype "bidirectional"))
      (node (ref "R59") (pin "1") (pinfunction "1_1") (pintype "passive"))
    )
    (net (code "39") (name "Net-(IC8-XTAL1)") (class "Default")
      (node (ref "C58") (pin "1") (pinfunction "1_1") (pintype "passive"))
      (node (ref "IC8") (pin "5") (pinfunction "XTAL1_5") (pintype "bidirectional"))
      (node (ref "Q3") (pin "2") (pinfunction "2_2") (pintype "passive"))
      (node (ref "R64") (pin "1") (pinfunction "1_1") (pintype "passive"))
    )
    (net (code "40") (name "Net-(IC8-XTAL2)") (class "Default")
      (node (ref "C59") (pin "1") (pinfunction "1_1") (pintype "passive"))
      (node (ref "IC8") (pin "4") (pinfunction "XTAL2_4") (pintype "bidirectional"))
      (node (ref "Q3") (pin "1") (pinfunction "1_1") (pintype "passive"))
      (node (ref "R64") (pin "2") (pinfunction "2_2") (pintype "passive"))
    )
    (net (code "41") (name "Net-(JP4-D+)") (class "Default")
      (node (ref "JP4") (pin "3") (pinfunction "D+_3") (pintype "bidirectional"))
      (node (ref "R8") (pin "1") (pinfunction "1_1") (pintype "passive"))
    )
    (net (code "42") (name "Net-(JP4-D-)") (class "Default")
      (node (ref "JP4") (pin "2") (pinfunction "D-_2") (pintype "bidirectional"))
      (node (ref "R9") (pin "1") (pinfunction "1_1") (pintype "passive"))
    )
    (net (code "43") (name "Net-(JP4-VCC)") (class "Default")
      (node (ref "JP4") (pin "1") (pinfunction "VCC_1") (pintype "bidirectional"))
      (node (ref "PTC1") (pin "2") (pinfunction "2_2") (pintype "passive"))
    )
    (net (code "44") (name "Net-(LED1-PadA)") (class "Default")
      (node (ref "LED1") (pin "A") (pinfunction "A_A") (pintype "passive"))
      (node (ref "R10") (pin "1") (pinfunction "1_1") (pintype "passive"))
    )
    (net (code "45") (name "Net-(LED2-PadA)") (class "Default")
      (node (ref "LED2") (pin "A") (pinfunction "A_A") (pintype "passive"))
      (node (ref "R11") (pin "1") (pinfunction "1_1") (pintype "passive"))
    )
    (net (code "46") (name "Net-(LED3-PadA)") (class "Default")
      (node (ref "LED3") (pin "A") (pinfunction "A_A") (pintype "passive"))
      (node (ref "R12") (pin "1") (pinfunction "1_1") (pintype "passive"))
    )
    (net (code "47") (name "Net-(LED4-PadA)") (class "Default")
      (node (ref "LED4") (pin "A") (pinfunction "A_A") (pintype "passive"))
      (node (ref "R13") (pin "1") (pinfunction "1_1") (pintype "passive"))
    )
    (net (code "48") (name "Net-(LED5-PadA)") (class "Default")
      (node (ref "LED5") (pin "A") (pinfunction "A_A") (pintype "passive"))
      (node (ref "R14") (pin "1") (pinfunction "1_1") (pintype "passive"))
    )
    (net (code "49") (name "Net-(Q1-D-Pad1)") (class "Default")
      (node (ref "Q1") (pin "1") (pinfunction "D_1") (pintype "passive"))
      (node (ref "Q1") (pin "2") (pinfunction "D_2") (pintype "passive"))
      (node (ref "Q1") (pin "5") (pinfunction "D_5") (pintype "passive"))
      (node (ref "Q1") (pin "6") (pinfunction "D_6") (pintype "passive"))
      (node (ref "R7") (pin "2") (pinfunction "2_2") (pintype "passive"))
    )
    (net (code "50") (name "Net-(R50-Pad2)") (class "Default")
      (node (ref "R50") (pin "2") (pinfunction "2_2") (pintype "passive"))
      (node (ref "RJ1") (pin "Y-") (pinfunction "Y-_Y-") (pintype "bidirectional"))
    )
    (net (code "51") (name "Net-(R61-Pad2)") (class "Default")
      (node (ref "R61") (pin "2") (pinfunction "2_2") (pintype "passive"))
      (node (ref "RJ1") (pin "G-") (pinfunction "G-_G-") (pintype "bidirectional"))
      (node (ref "RJ1") (pin "G--") (pinfunction "G-_G--") (pintype "bidirectional"))
    )
    (net (code "52") (name "RD+") (class "Default")
      (node (ref "C56") (pin "1") (pinfunction "1_1") (pintype "passive"))
      (node (ref "IC8") (pin "23") (pinfunction "RX+_23") (pintype "bidirectional"))
      (node (ref "R56") (pin "2") (pinfunction "2_2") (pintype "passive"))
      (node (ref "RJ1") (pin "RD+") (pinfunction "RD+_RD+") (pintype "bidirectional"))
    )
    (net (code "53") (name "RD-") (class "Default")
      (node (ref "C57") (pin "1") (pinfunction "1_1") (pintype "passive"))
      (node (ref "IC8") (pin "22") (pinfunction "RX-_22") (pintype "bidirectional"))
      (node (ref "R57") (pin "2") (pinfunction "2_2") (pintype "passive"))
      (node (ref "RJ1") (pin "RD-") (pinfunction "RD-_RD-") (pintype "bidirectional"))
    )
    (net (code "54") (name "RTCK") (class "Default")
      (node (ref "IC1") (pin "100") (pinfunction "RTCK_100") (pintype "bidirectional"))
      (node (ref "JTAG2") (pin "7") (pinfunction "7_7") (pintype "passive"))
    )
    (net (code "55") (name "RX_0") (class "Default")
      (node (ref "IC1") (pin "99") (pinfunction "P0[3]/RXD0/AD0[6]_99") (pintype "bidirectional"))
      (node (ref "JP3") (pin "4") (pinfunction "4_4") (pintype "passive"))
    )
    (net (code "56") (name "SCL") (class "Default")
      (node (ref "IC1") (pin "24") (pinfunction "P0[28]/SCL0/USB_SCL_24") (pintype "bidirectional"))
      (node (ref "U1") (pin "SCL1") (pinfunction "SCL_SCL1") (pintype "bidirectional"))
    )
    (net (code "57") (name "SDA") (class "Default")
      (node (ref "IC1") (pin "25") (pinfunction "P0[27]/SDA0/USB_SDA_25") (pintype "bidirectional"))
      (node (ref "U1") (pin "SDA1") (pinfunction "SDA_SDA1") (pintype "bidirectional"))
    )
    (net (code "58") (name "SD_CS") (class "Default")
      (node (ref "IC1") (pin "79") (pinfunction "P0[6]/I2SRX_SDA/SSEL1/MAT2[0]_79") (pintype "bidirectional"))
      (node (ref "X1") (pin "2") (pinfunction "D3_2") (pintype "bidirectional"))
    )
    (net (code "59") (name "SD_MISO") (class "Default")
      (node (ref "IC1") (pin "77") (pinfunction "P0[8]/I2STX_WS/MISO1/MAT2[2]_77") (pintype "bidirectional"))
      (node (ref "U1") (pin "MISO") (pinfunction "MISO_MISO") (pintype "bidirectional"))
      (node (ref "X1") (pin "7") (pinfunction "D0_7") (pintype "bidirectional"))
    )
    (net (code "60") (name "SD_MOSI") (class "Default")
      (node (ref "IC1") (pin "76") (pinfunction "P0[9]/I2STX_SDA/MOSI1/MAT2[3]_76") (pintype "bidirectional"))
      (node (ref "U1") (pin "MOSI") (pinfunction "MOSI_MOSI") (pintype "bidirectional"))
      (node (ref "X1") (pin "3") (pinfunction "CMD_3") (pintype "bidirectional"))
    )
    (net (code "61") (name "SD_SCK") (class "Default")
      (node (ref "IC1") (pin "78") (pinfunction "P0[7]/I2STX_CLK/SCK1/MAT2[1]_78") (pintype "bidirectional"))
      (node (ref "U1") (pin "SCK") (pinfunction "SCK_SCK") (pintype "bidirectional"))
      (node (ref "X1") (pin "5") (pinfunction "CLK_5") (pintype "input"))
    )
    (net (code "62") (name "SERVO1") (class "Default")
      (node (ref "IC1") (pin "27") (pinfunction "P3[25]/MAT0[0]/PWM1[2]_27") (pintype "bidirectional"))
      (node (ref "U1") (pin "4") (pinfunction "4_4") (pintype "bidirectional"))
    )
    (net (code "63") (name "SERVO2") (class "Default")
      (node (ref "IC1") (pin "26") (pinfunction "P3[26]/STCLK/MAT0[1]/PWM1[3]_26") (pintype "bidirectional"))
      (node (ref "U1") (pin "5") (pinfunction "5_5") (pintype "bidirectional"))
    )
    (net (code "64") (name "SERVO3") (class "Default")
      (node (ref "IC1") (pin "68") (pinfunction "P2[5]/PWM1[6]/DTR1/TRACEDATA[0]_68") (pintype "bidirectional"))
      (node (ref "U1") (pin "6") (pinfunction "6_6") (pintype "bidirectional"))
    )
    (net (code "65") (name "SERVO4") (class "Default")
      (node (ref "IC1") (pin "69") (pinfunction "P2[4]/PWM1[5]/DSR1/TRACEDATA[1]_69") (pintype "bidirectional"))
      (node (ref "U1") (pin "7") (pinfunction "7_7") (pintype "bidirectional"))
    )
    (net (code "66") (name "SPAREIO_0") (class "Default")
      (node (ref "IC1") (pin "66") (pinfunction "P2[7]/RD2/RTS1_66") (pintype "bidirectional"))
      (node (ref "U1") (pin "23") (pinfunction "23_23") (pintype "bidirectional"))
    )
    (net (code "67") (name "SPAREIO_1") (class "Default")
      (node (ref "IC1") (pin "65") (pinfunction "P2[8]/TD2/TXD2_65") (pintype "bidirectional"))
      (node (ref "U1") (pin "25") (pinfunction "25_25") (pintype "bidirectional"))
    )
    (net (code "68") (name "SPAREIO_2") (class "Default")
      (node (ref "IC1") (pin "62") (pinfunction "P0[15]/TXD1/SCK0/SCK_62") (pintype "bidirectional"))
      (node (ref "U1") (pin "27") (pinfunction "27_27") (pintype "bidirectional"))
    )
    (net (code "69") (name "SPAREIO_3") (class "Default")
      (node (ref "IC1") (pin "63") (pinfunction "P0[16]/RXD1/SSEL0/SSEL_63") (pintype "bidirectional"))
      (node (ref "U1") (pin "29") (pinfunction "29_29") (pintype "bidirectional"))
    )
    (net (code "70") (name "SPAREIO_4") (class "Default")
      (node (ref "IC1") (pin "61") (pinfunction "P0[17]/CTS1/MISO0/MISO_61") (pintype "bidirectional"))
      (node (ref "U1") (pin "31") (pinfunction "31_31") (pintype "bidirectional"))
    )
    (net (code "71") (name "SPAREIO_5") (class "Default")
      (node (ref "IC1") (pin "60") (pinfunction "P0[18]/DCD1/MOSI0/MOSI_60") (pintype "bidirectional"))
      (node (ref "U1") (pin "33") (pinfunction "33_33") (pintype "bidirectional"))
    )
    (net (code "72") (name "SPAREIO_6") (class "Default")
      (node (ref "IC1") (pin "37") (pinfunction "P1[23]/MCFB1/PWM1[4]/MISO0_37") (pintype "bidirectional"))
      (node (ref "U1") (pin "35") (pinfunction "35_35") (pintype "bidirectional"))
    )
    (net (code "73") (name "SPAREIO_7") (class "Default")
      (node (ref "IC1") (pin "36") (pinfunction "P1[22]/MC0B/USB_PWRD/MAT1[0]_36") (pintype "bidirectional"))
      (node (ref "U1") (pin "37") (pinfunction "37_37") (pintype "bidirectional"))
    )
    (net (code "74") (name "SPAREIO_8") (class "Default")
      (node (ref "IC1") (pin "43") (pinfunction "P1[27]/CLKOUT/USB_OVRCR/CAP0[1]_43") (pintype "bidirectional"))
      (node (ref "U1") (pin "39") (pinfunction "39_39") (pintype "bidirectional"))
    )
    (net (code "75") (name "STP1") (class "Default")
      (node (ref "IC1") (pin "75") (pinfunction "P2[0]/PWM1[1]/TXD1_75") (pintype "bidirectional"))
      (node (ref "U1") (pin "38") (pinfunction "38_38") (pintype "bidirectional"))
    )
    (net (code "76") (name "STP2") (class "Default")
      (node (ref "IC1") (pin "74") (pinfunction "P2[1]/PWM1[2]/RXD1_74") (pintype "bidirectional"))
      (node (ref "U1") (pin "A2") (pinfunction "A2_A2") (pintype "bidirectional"))
    )
    (net (code "77") (name "STP3") (class "Default")
      (node (ref "IC1") (pin "73") (pinfunction "P2[2]/PWM1[3]/CTS1/TRACEDATA[3]_73") (pintype "bidirectional"))
      (node (ref "U1") (pin "9") (pinfunction "9_9") (pintype "bidirectional"))
    )
    (net (code "78") (name "STP4") (class "Default")
      (node (ref "IC1") (pin "70") (pinfunction "P2[3]/PWM1[4]/DCD1/TRACEDATA[2]_70") (pintype "bidirectional"))
      (node (ref "U1") (pin "30") (pinfunction "30_30") (pintype "bidirectional"))
    )
    (net (code "79") (name "TCK-SWDCLK") (class "Default")
      (node (ref "IC1") (pin "5") (pinfunction "TCK/SWDCLK_5") (pintype "bidirectional"))
      (node (ref "JTAG2") (pin "4") (pinfunction "4_4") (pintype "passive"))
    )
    (net (code "80") (name "TD+") (class "Default")
      (node (ref "C54") (pin "1") (pinfunction "1_1") (pintype "passive"))
      (node (ref "IC8") (pin "21") (pinfunction "TX+_21") (pintype "bidirectional"))
      (node (ref "R54") (pin "2") (pinfunction "2_2") (pintype "passive"))
      (node (ref "RJ1") (pin "TD+") (pinfunction "TD+_TD+") (pintype "bidirectional"))
    )
    (net (code "81") (name "TD-") (class "Default")
      (node (ref "C55") (pin "1") (pinfunction "1_1") (pintype "passive"))
      (node (ref "IC8") (pin "20") (pinfunction "TX-_20") (pintype "bidirectional"))
      (node (ref "R55") (pin "2") (pinfunction "2_2") (pintype "passive"))
      (node (ref "RJ1") (pin "TD-") (pinfunction "TD-_TD-") (pintype "bidirectional"))
    )
    (net (code "82") (name "TDI") (class "Default")
      (node (ref "IC1") (pin "2") (pinfunction "TDI_2") (pintype "bidirectional"))
      (node (ref "JTAG2") (pin "8") (pinfunction "8_8") (pintype "passive"))
    )
    (net (code "83") (name "TDO-SWO") (class "Default")
      (node (ref "IC1") (pin "1") (pinfunction "TDO/SWO_1") (pintype "bidirectional"))
      (node (ref "JTAG2") (pin "6") (pinfunction "6_6") (pintype "passive"))
    )
    (net (code "84") (name "TMS-SWDIO") (class "Default")
      (node (ref "IC1") (pin "3") (pinfunction "TMS/SWDIO_3") (pintype "bidirectional"))
      (node (ref "JTAG2") (pin "2") (pinfunction "2_2") (pintype "passive"))
    )
    (net (code "85") (name "TOOL1_AIN") (class "Default")
      (node (ref "IC1") (pin "9") (pinfunction "P0[23]/AD0[0]/I2SRX_CLK/CAP3[0]_9") (pintype "bidirectional"))
      (node (ref "U1") (pin "A12") (pinfunction "A12_A12") (pintype "bidirectional"))
    )
    (net (code "86") (name "TOOL1_DOUT") (class "Default")
      (node (ref "IC1") (pin "39") (pinfunction "P1[25]/MC1A/MAT1[1]_39") (pintype "bidirectional"))
      (node (ref "U1") (pin "42") (pinfunction "42_42") (pintype "bidirectional"))
    )
    (net (code "87") (name "TOOL2_AIN") (class "Default")
      (node (ref "IC1") (pin "8") (pinfunction "P0[24]/AD0[1]/I2SRX_WS/CAP3[1]_8") (pintype "bidirectional"))
      (node (ref "U1") (pin "A13") (pinfunction "A13_A13") (pintype "bidirectional"))
    )
    (net (code "88") (name "TOOL2_DOUT") (class "Default")
      (node (ref "IC1") (pin "82") (pinfunction "P4[28]/RX_MCLK/MAT2[0]/TXD3_82") (pintype "bidirectional"))
      (node (ref "U1") (pin "50") (pinfunction "50_50") (pintype "bidirectional"))
    )
    (net (code "89") (name "TOOL3_AIN") (class "Default")
      (node (ref "IC1") (pin "7") (pinfunction "P0[25]/AD0[2]/I2SRX_SDA/TXD3_7") (pintype "bidirectional"))
      (node (ref "U1") (pin "A15") (pinfunction "A15_A15") (pintype "bidirectional"))
    )
    (net (code "90") (name "TOOL3_DOUT") (class "Default")
      (node (ref "IC1") (pin "47") (pinfunction "P0[1]/TD1/RXD3/SCL1_47") (pintype "bidirectional"))
      (node (ref "U1") (pin "22") (pinfunction "22_22") (pintype "bidirectional"))
    )
    (net (code "91") (name "TOOL4_AIN") (class "Default")
      (node (ref "IC1") (pin "6") (pinfunction "P0[26]/AD0[3]/AOUT/RXD3_6") (pintype "bidirectional"))
      (node (ref "U1") (pin "A14") (pinfunction "A14_A14") (pintype "bidirectional"))
    )
    (net (code "92") (name "TOOL4_DOUT") (class "Default")
      (node (ref "IC1") (pin "51") (pinfunction "P2[12]/EINT2/I2STX_WS_51") (pintype "bidirectional"))
      (node (ref "U1") (pin "18") (pinfunction "18(TX1)_18") (pintype "bidirectional"))
    )
    (net (code "93") (name "TX_0") (class "Default")
      (node (ref "IC1") (pin "98") (pinfunction "P0[2]/TXD0/AD0[7]_98") (pintype "bidirectional"))
      (node (ref "JP3") (pin "5") (pinfunction "5_5") (pintype "passive"))
    )
    (net (code "94") (name "USB_CONNECT") (class "Default")
      (node (ref "IC1") (pin "64") (pinfunction "P2[9]/USB_CONNECT/RXD2_64") (pintype "bidirectional"))
      (node (ref "Q1") (pin "3") (pinfunction "G_3") (pintype "passive"))
    )
    (net (code "95") (name "USB_N") (class "Default")
      (node (ref "C4") (pin "2") (pinfunction "2_2") (pintype "passive"))
      (node (ref "IC1") (pin "30") (pinfunction "P0[30]/USB_D-_30") (pintype "bidirectional"))
      (node (ref "R9") (pin "2") (pinfunction "2_2") (pintype "passive"))
    )
    (net (code "96") (name "USB_P") (class "Default")
      (node (ref "C5") (pin "2") (pinfunction "2_2") (pintype "passive"))
      (node (ref "IC1") (pin "29") (pinfunction "P0[29]/USB_D+_29") (pintype "bidirectional"))
      (node (ref "R7") (pin "1") (pinfunction "1_1") (pintype "passive"))
      (node (ref "R8") (pin "2") (pinfunction "2_2") (pintype "passive"))
    )
    (net (code "97") (name "VSENSE") (class "Default")
      (node (ref "IC1") (pin "21") (pinfunction "P1[30]/VBUS/AD0[4]_21") (pintype "bidirectional"))
      (node (ref "U1") (pin "A1") (pinfunction "A1(TX0)_A1") (pintype "bidirectional"))
    )
    (net (code "98") (name "VUSB") (class "Default")
      (node (ref "D1") (pin "A") (pinfunction "A_A") (pintype "passive"))
      (node (ref "PTC1") (pin "1") (pinfunction "1_1") (pintype "passive"))
    )
    (net (code "99") (name "X_MIN") (class "Default")
      (node (ref "IC1") (pin "38") (pinfunction "P1[24]/MCFB2/PWM1[5]/MOSI0_38") (pintype "bidirectional"))
      (node (ref "U1") (pin "A9") (pinfunction "A9_A9") (pintype "bidirectional"))
    )
    (net (code "100") (name "Y_MIN") (class "Default")
      (node (ref "IC1") (pin "40") (pinfunction "P1[26]/MC1B/PWM1[6]/CAP0[0]_40") (pintype "bidirectional"))
      (node (ref "U1") (pin "A10") (pinfunction "A10_A10") (pintype "bidirectional"))
    )
    (net (code "101") (name "Z_MIN") (class "Default")
      (node (ref "IC1") (pin "44") (pinfunction "P1[28]/MC2A/PCAP1[0]/MAT0[0]_44") (pintype "bidirectional"))
      (node (ref "U1") (pin "A11") (pinfunction "A11_A11") (pintype "bidirectional"))
    )
    (net (code "102") (name "unconnected-(IC1-N.C.-Pad13)") (class "Default")
      (node (ref "IC1") (pin "13") (pinfunction "N.C._13") (pintype "bidirectional"))
    )
    (net (code "103") (name "unconnected-(IC1-RTCX1-Pad16)") (class "Default")
      (node (ref "IC1") (pin "16") (pinfunction "RTCX1_16") (pintype "bidirectional"))
    )
    (net (code "104") (name "unconnected-(IC1-RTCX2-Pad18)") (class "Default")
      (node (ref "IC1") (pin "18") (pinfunction "RTCX2_18") (pintype "bidirectional"))
    )
    (net (code "105") (name "unconnected-(IC1-TRST-Pad4)") (class "Default")
      (node (ref "IC1") (pin "4") (pinfunction "TRST_4") (pintype "bidirectional"))
    )
    (net (code "106") (name "unconnected-(IC7-NC-Pad1)") (class "Default")
      (node (ref "IC7") (pin "1") (pinfunction "NC_1") (pintype "no_connect"))
    )
    (net (code "107") (name "unconnected-(JP3-Pad2)") (class "Default")
      (node (ref "JP3") (pin "2") (pinfunction "2_2") (pintype "passive"))
    )
    (net (code "108") (name "unconnected-(JP3-Pad3)") (class "Default")
      (node (ref "JP3") (pin "3") (pinfunction "3_3") (pintype "passive"))
    )
    (net (code "109") (name "unconnected-(JP3-Pad6)") (class "Default")
      (node (ref "JP3") (pin "6") (pinfunction "6_6") (pintype "passive"))
    )
    (net (code "110") (name "unconnected-(JP4-ID-Pad4)") (class "Default")
      (node (ref "JP4") (pin "4") (pinfunction "ID_4") (pintype "bidirectional"))
    )
    (net (code "111") (name "unconnected-(JP4-SHIELD-Pad7)") (class "Default")
      (node (ref "JP4") (pin "7") (pinfunction "SHIELD_7") (pintype "bidirectional"))
    )
    (net (code "112") (name "unconnected-(JP4-SHIELD-Pad11)") (class "Default")
      (node (ref "JP4") (pin "11") (pinfunction "SHIELD_11") (pintype "bidirectional"))
    )
    (net (code "113") (name "unconnected-(JP4-SHIELD-Pad12)") (class "Default")
      (node (ref "JP4") (pin "12") (pinfunction "SHIELD_12") (pintype "bidirectional"))
    )
    (net (code "114") (name "unconnected-(JP4-SHIELD-Pad17)") (class "Default")
      (node (ref "JP4") (pin "17") (pinfunction "SHIELD_17") (pintype "bidirectional"))
    )
    (net (code "115") (name "unconnected-(RJ1-PadNC)") (class "Default")
      (node (ref "RJ1") (pin "NC") (pinfunction "NC_NC") (pintype "bidirectional"))
    )
    (net (code "116") (name "unconnected-(U1-0(RX0)-Pad0)") (class "Default")
      (node (ref "U1") (pin "0") (pinfunction "0(RX0)_0") (pintype "bidirectional"))
    )
    (net (code "117") (name "unconnected-(U1-1(TX0)-Pad1)") (class "Default")
      (node (ref "U1") (pin "1") (pinfunction "1(TX0)_1") (pintype "bidirectional"))
    )
    (net (code "118") (name "unconnected-(U1-14(TX3)-Pad14)") (class "Default")
      (node (ref "U1") (pin "14") (pinfunction "14(TX3)_14") (pintype "bidirectional"))
    )
    (net (code "119") (name "unconnected-(U1-15(RX3)-Pad15)") (class "Default")
      (node (ref "U1") (pin "15") (pinfunction "15(RX3)_15") (pintype "bidirectional"))
    )
    (net (code "120") (name "unconnected-(U1-16(TX2)-Pad16)") (class "Default")
      (node (ref "U1") (pin "16") (pinfunction "16(TX2)_16") (pintype "bidirectional"))
    )
    (net (code "121") (name "unconnected-(U1-17(RX2)-Pad17)") (class "Default")
      (node (ref "U1") (pin "17") (pinfunction "17(RX2)_17") (pintype "bidirectional"))
    )
    (net (code "122") (name "unconnected-(U1-20(SDA)-Pad20)") (class "Default")
      (node (ref "U1") (pin "20") (pinfunction "20(SDA)_20") (pintype "bidirectional"))
    )
    (net (code "123") (name "unconnected-(U1-21(SCL)-Pad21)") (class "Default")
      (node (ref "U1") (pin "21") (pinfunction "21(SCL)_21") (pintype "bidirectional"))
    )
    (net (code "124") (name "unconnected-(U1-Pad3)") (class "Default")
      (node (ref "U1") (pin "3") (pinfunction "3_3") (pintype "bidirectional"))
    )
    (net (code "125") (name "unconnected-(U1-Pad10)") (class "Default")
      (node (ref "U1") (pin "10") (pinfunction "10_10") (pintype "bidirectional"))
    )
    (net (code "126") (name "unconnected-(U1-Pad11)") (class "Default")
      (node (ref "U1") (pin "11") (pinfunction "11_11") (pintype "bidirectional"))
    )
    (net (code "127") (name "unconnected-(U1-Pad26)") (class "Default")
      (node (ref "U1") (pin "26") (pinfunction "26_26") (pintype "bidirectional"))
    )
    (net (code "128") (name "unconnected-(U1-Pad34)") (class "Default")
      (node (ref "U1") (pin "34") (pinfunction "34_34") (pintype "bidirectional"))
    )
    (net (code "129") (name "unconnected-(U1-Pad41)") (class "Default")
      (node (ref "U1") (pin "41") (pinfunction "41_41") (pintype "bidirectional"))
    )
    (net (code "130") (name "unconnected-(U1-Pad43)") (class "Default")
      (node (ref "U1") (pin "43") (pinfunction "43_43") (pintype "bidirectional"))
    )
    (net (code "131") (name "unconnected-(U1-Pad45)") (class "Default")
      (node (ref "U1") (pin "45") (pinfunction "45_45") (pintype "bidirectional"))
    )
    (net (code "132") (name "unconnected-(U1-Pad46)") (class "Default")
      (node (ref "U1") (pin "46") (pinfunction "46_46") (pintype "bidirectional"))
    )
    (net (code "133") (name "unconnected-(U1-Pad47)") (class "Default")
      (node (ref "U1") (pin "47") (pinfunction "47_47") (pintype "bidirectional"))
    )
    (net (code "134") (name "unconnected-(U1-Pad48)") (class "Default")
      (node (ref "U1") (pin "48") (pinfunction "48_48") (pintype "bidirectional"))
    )
    (net (code "135") (name "unconnected-(U1-Pad49)") (class "Default")
      (node (ref "U1") (pin "49") (pinfunction "49_49") (pintype "bidirectional"))
    )
    (net (code "136") (name "unconnected-(U1-Pad51)") (class "Default")
      (node (ref "U1") (pin "51") (pinfunction "51_51") (pintype "bidirectional"))
    )
    (net (code "137") (name "unconnected-(U1-Pad53)") (class "Default")
      (node (ref "U1") (pin "53") (pinfunction "53_53") (pintype "bidirectional"))
    )
    (net (code "138") (name "unconnected-(U1-PadA4)") (class "Default")
      (node (ref "U1") (pin "A4") (pinfunction "A4_A4") (pintype "bidirectional"))
    )
    (net (code "139") (name "unconnected-(U1-PadA5)") (class "Default")
      (node (ref "U1") (pin "A5") (pinfunction "A5_A5") (pintype "bidirectional"))
    )
    (net (code "140") (name "unconnected-(U1-PadA6)") (class "Default")
      (node (ref "U1") (pin "A6") (pinfunction "A6_A6") (pintype "bidirectional"))
    )
    (net (code "141") (name "unconnected-(U1-PadA7)") (class "Default")
      (node (ref "U1") (pin "A7") (pinfunction "A7_A7") (pintype "bidirectional"))
    )
    (net (code "142") (name "unconnected-(U1-PadAREF)") (class "Default")
      (node (ref "U1") (pin "AREF") (pinfunction "AREF_AREF") (pintype "bidirectional"))
    )
    (net (code "143") (name "unconnected-(U1-PadVIN)") (class "Default")
      (node (ref "U1") (pin "VIN") (pinfunction "VIN_VIN") (pintype "bidirectional"))
    )
    (net (code "144") (name "unconnected-(X1-D1-Pad8)") (class "Default")
      (node (ref "X1") (pin "8") (pinfunction "D1_8") (pintype "bidirectional"))
    )
    (net (code "145") (name "unconnected-(X1-D2-Pad1)") (class "Default")
      (node (ref "X1") (pin "1") (pinfunction "D2_1") (pintype "bidirectional"))
    )
    (net (code "146") (name "~{EN1}") (class "Default")
      (node (ref "IC1") (pin "81") (pinfunction "P0[4]/I2SRX_CLK/RD2/CAP2[0]_81") (pintype "bidirectional"))
      (node (ref "U1") (pin "40") (pinfunction "40_40") (pintype "bidirectional"))
    )
    (net (code "147") (name "~{EN2}") (class "Default")
      (node (ref "IC1") (pin "48") (pinfunction "P0[10]/TXD2/SDA2/MAT3[0]_48") (pintype "bidirectional"))
      (node (ref "U1") (pin "A0") (pinfunction "A0(RX0)_A0") (pintype "bidirectional"))
    )
    (net (code "148") (name "~{EN3}") (class "Default")
      (node (ref "IC1") (pin "59") (pinfunction "P0[19]/DSR1/SDA1_59") (pintype "bidirectional"))
      (node (ref "U1") (pin "2") (pinfunction "2_2") (pintype "bidirectional"))
    )
    (net (code "149") (name "~{EN4}") (class "Default")
      (node (ref "IC1") (pin "57") (pinfunction "P0[21]/RI1/RD1_57") (pintype "bidirectional"))
      (node (ref "U1") (pin "44") (pinfunction "44_44") (pintype "bidirectional"))
    )
    (net (code "150") (name "~{PS_ON}") (class "Default")
      (node (ref "IC1") (pin "45") (pinfunction "P1[29]/MC2B/PCAP1[1]/MAT0[1]_45") (pintype "bidirectional"))
      (node (ref "U1") (pin "28") (pinfunction "28_28") (pintype "bidirectional"))
    )
    (net (code "151") (name "~{RSTOUT}") (class "Default")
      (node (ref "IC1") (pin "14") (pinfunction "RSTOUT_14") (pintype "bidirectional"))
      (node (ref "IC8") (pin "15") (pinfunction "NRST_15") (pintype "bidirectional"))
    )
    (net (code "152") (name "~{RST}") (class "Default")
      (node (ref "IC1") (pin "17") (pinfunction "RESET_17") (pintype "bidirectional"))
      (node (ref "JP1") (pin "2") (pinfunction "2_2") (pintype "passive"))
      (node (ref "JTAG2") (pin "10") (pinfunction "10_10") (pintype "passive"))
      (node (ref "R4") (pin "1") (pinfunction "1_1") (pintype "passive"))
      (node (ref "S1") (pin "1") (pinfunction "1_1") (pintype "passive"))
      (node (ref "S1") (pin "2") (pinfunction "2_2") (pintype "passive"))
      (node (ref "S3") (pin "1") (pinfunction "1_1") (pintype "passive"))
      (node (ref "S3") (pin "2") (pinfunction "2_2") (pintype "passive"))
      (node (ref "U1") (pin "RESET") (pinfunction "RESET_RESET") (pintype "bidirectional"))
      (node (ref "U1") (pin "RST") (pinfunction "RESET_RST") (pintype "bidirectional"))
    )
    (net (code "153") (name "~{TOOL2_EN}") (class "Default")
      (node (ref "IC1") (pin "85") (pinfunction "P4[29]/TX_MCLK/MAT2[1]/RXD3_85") (pintype "bidirectional"))
      (node (ref "U1") (pin "52") (pinfunction "52_52") (pintype "bidirectional"))
    )
    (net (code "154") (name "~{TOOL3_EN}") (class "Default")
      (node (ref "IC1") (pin "46") (pinfunction "P0[0]/RD1/TXD3/SDA1_46") (pintype "bidirectional"))
      (node (ref "U1") (pin "24") (pinfunction "24_24") (pintype "bidirectional"))
    )
    (net (code "155") (name "~{TOOL4_EN}") (class "Default")
      (node (ref "IC1") (pin "50") (pinfunction "P2[13]/EINT3/I2STX_SDA_50") (pintype "bidirectional"))
      (node (ref "U1") (pin "19") (pinfunction "19(RX1)_19") (pintype "bidirectional"))
    )
  )
)
